# fpga.net
KiCad netlist of a schematic drawn in Altium Designer
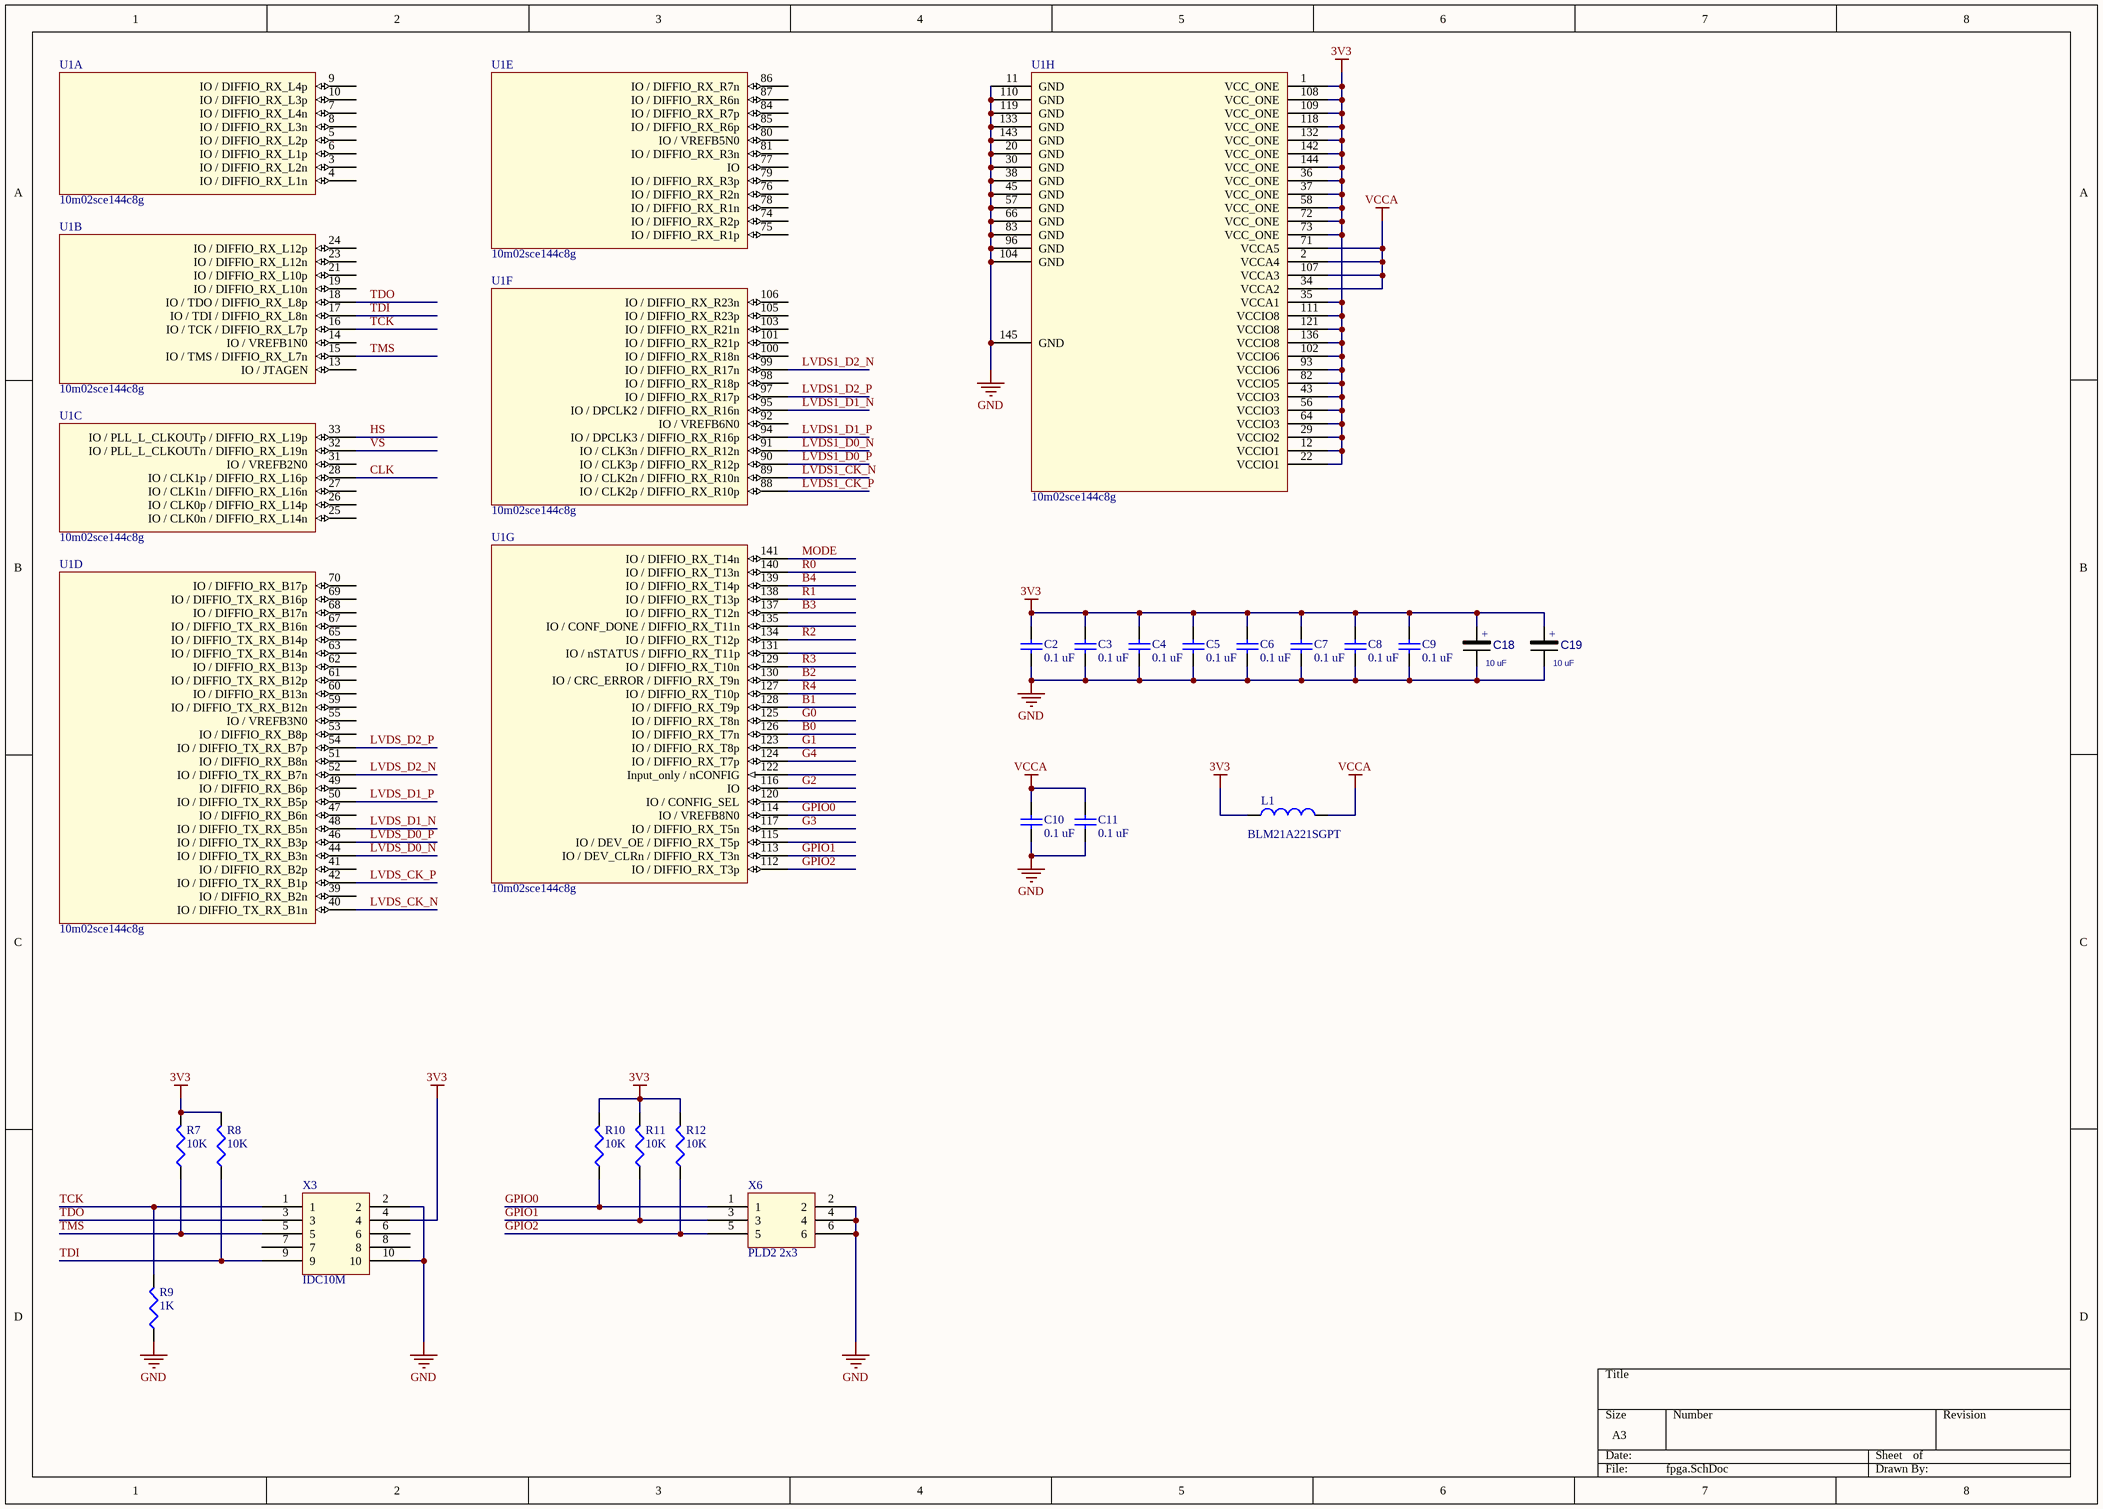
[diagram p0: fpga.SchDoc]

(export (version "E")
  (design (tool "Eeschema 10.0.6"))
  (components
    (comp (ref "C2")
      (value "0.1 uF")
      (footprint "0805 chip cap")
      (description "Capacitor")
      (libsource (lib "Schlib") (part "Cap"))
    )
    (comp (ref "C3")
      (value "0.1 uF")
      (footprint "0805 chip cap")
      (description "Capacitor")
      (libsource (lib "Schlib") (part "Cap"))
    )
    (comp (ref "C4")
      (value "0.1 uF")
      (footprint "0805 chip cap")
      (description "Capacitor")
      (libsource (lib "Schlib") (part "Cap"))
    )
    (comp (ref "C5")
      (value "0.1 uF")
      (footprint "0805 chip cap")
      (description "Capacitor")
      (libsource (lib "Schlib") (part "Cap"))
    )
    (comp (ref "C6")
      (value "0.1 uF")
      (footprint "0805 chip cap")
      (description "Capacitor")
      (libsource (lib "Schlib") (part "Cap"))
    )
    (comp (ref "C7")
      (value "0.1 uF")
      (footprint "0805 chip cap")
      (description "Capacitor")
      (libsource (lib "Schlib") (part "Cap"))
    )
    (comp (ref "C8")
      (value "0.1 uF")
      (footprint "0805 chip cap")
      (description "Capacitor")
      (libsource (lib "Schlib") (part "Cap"))
    )
    (comp (ref "C9")
      (value "0.1 uF")
      (footprint "0805 chip cap")
      (description "Capacitor")
      (libsource (lib "Schlib") (part "Cap"))
    )
    (comp (ref "C10")
      (value "0.1 uF")
      (footprint "0805 chip cap")
      (description "Capacitor")
      (libsource (lib "Schlib") (part "Cap"))
    )
    (comp (ref "C11")
      (value "0.1 uF")
      (footprint "0805 chip cap")
      (description "Capacitor")
      (libsource (lib "Schlib") (part "Cap"))
    )
    (comp (ref "C18")
      (value "10 uF")
      (footprint "CAP CASE-A")
      (libsource (lib "Schlib") (part "CAP POL CASE A"))
    )
    (comp (ref "C19")
      (value "10 uF")
      (footprint "CAP CASE-A")
      (libsource (lib "Schlib") (part "CAP POL CASE A"))
    )
    (comp (ref "L1")
      (value "BLM21A221SGPT")
      (footprint "0805 CHIP RES")
      (description "CHIP FERRITE BEADS 220R AT 100Mhz")
      (libsource (lib "Schlib") (part "BLM21A221SGPT"))
    )
    (comp (ref "R7")
      (value "10K")
      (footprint "0805 CHIP RES")
      (description "Resistor")
      (libsource (lib "Schlib") (part "CHIP RES"))
    )
    (comp (ref "R8")
      (value "10K")
      (footprint "0805 CHIP RES")
      (description "Resistor")
      (libsource (lib "Schlib") (part "CHIP RES"))
    )
    (comp (ref "R9")
      (value "1K")
      (footprint "0805 CHIP RES")
      (description "Resistor")
      (libsource (lib "Schlib") (part "CHIP RES"))
    )
    (comp (ref "R10")
      (value "10K")
      (footprint "0805 CHIP RES")
      (description "Resistor")
      (libsource (lib "Schlib") (part "CHIP RES"))
    )
    (comp (ref "R11")
      (value "10K")
      (footprint "0805 CHIP RES")
      (description "Resistor")
      (libsource (lib "Schlib") (part "CHIP RES"))
    )
    (comp (ref "R12")
      (value "10K")
      (footprint "0805 CHIP RES")
      (description "Resistor")
      (libsource (lib "Schlib") (part "CHIP RES"))
    )
    (comp (ref "U1")
      (value "10m02sce144c8g")
      (footprint "Altera TQFP 50P 22X22 145N")
      (description "FPGA MAX10")
      (libsource (lib "Schlib") (part "10m02sce144c8g"))
    )
    (comp (ref "X3") (value "IDC10M") (footprint "PLD2-10") (libsource (lib "Schlib") (part "PLD2-10")))
    (comp (ref "X6") (value "PLD2 2x3") (footprint "PLD2-6") (libsource (lib "Schlib") (part "PLD2-6")))
  )
  (nets
    (net (code "1") (name "/B0") (class "Default")
      (node (ref "U1") (pin "126") (pinfunction "IO_/_DIFFIO_RX_T7n_126") (pintype "bidirectional"))
    )
    (net (code "2") (name "/B1") (class "Default")
      (node (ref "U1") (pin "128") (pinfunction "IO_/_DIFFIO_RX_T9p_128") (pintype "bidirectional"))
    )
    (net (code "3") (name "/B2") (class "Default")
      (node (ref "U1") (pin "130") (pinfunction "IO_/_CRC_ERROR_/_DIFFIO_RX_T9n_130") (pintype "bidirectional"))
    )
    (net (code "4") (name "/B3") (class "Default")
      (node (ref "U1") (pin "137") (pinfunction "IO_/_DIFFIO_RX_T12n_137") (pintype "bidirectional"))
    )
    (net (code "5") (name "/B4") (class "Default")
      (node (ref "U1") (pin "139") (pinfunction "IO_/_DIFFIO_RX_T14p_139") (pintype "bidirectional"))
    )
    (net (code "6") (name "/CLK") (class "Default")
      (node (ref "U1") (pin "28") (pinfunction "IO_/_CLK1p_/_DIFFIO_RX_L16p_28") (pintype "bidirectional"))
    )
    (net (code "7") (name "/G0") (class "Default")
      (node (ref "U1") (pin "125") (pinfunction "IO_/_DIFFIO_RX_T8n_125") (pintype "bidirectional"))
    )
    (net (code "8") (name "/G1") (class "Default")
      (node (ref "U1") (pin "123") (pinfunction "IO_/_DIFFIO_RX_T8p_123") (pintype "bidirectional"))
    )
    (net (code "9") (name "/G2") (class "Default")
      (node (ref "U1") (pin "116") (pinfunction "IO_116") (pintype "bidirectional"))
    )
    (net (code "10") (name "/G3") (class "Default")
      (node (ref "U1") (pin "117") (pinfunction "IO_/_DIFFIO_RX_T5n_117") (pintype "bidirectional"))
    )
    (net (code "11") (name "/G4") (class "Default")
      (node (ref "U1") (pin "124") (pinfunction "IO_/_DIFFIO_RX_T7p_124") (pintype "bidirectional"))
    )
    (net (code "12") (name "/GPIO0") (class "Default")
      (node (ref "R10") (pin "1") (pinfunction "1_1") (pintype "passive"))
      (node (ref "U1") (pin "114") (pinfunction "IO_/_VREFB8N0_114") (pintype "bidirectional"))
      (node (ref "X6") (pin "1") (pinfunction "1_1") (pintype "passive"))
    )
    (net (code "13") (name "/GPIO1") (class "Default")
      (node (ref "R11") (pin "1") (pinfunction "1_1") (pintype "passive"))
      (node (ref "U1") (pin "113") (pinfunction "IO_/_DEV_CLRn_/_DIFFIO_RX_T3n_113") (pintype "bidirectional"))
      (node (ref "X6") (pin "3") (pinfunction "3_3") (pintype "passive"))
    )
    (net (code "14") (name "/GPIO2") (class "Default")
      (node (ref "R12") (pin "1") (pinfunction "1_1") (pintype "passive"))
      (node (ref "U1") (pin "112") (pinfunction "IO_/_DIFFIO_RX_T3p_112") (pintype "bidirectional"))
      (node (ref "X6") (pin "5") (pinfunction "5_5") (pintype "passive"))
    )
    (net (code "15") (name "/HS") (class "Default")
      (node (ref "U1") (pin "33") (pinfunction "IO_/_PLL_L_CLKOUTp_/_DIFFIO_RX_L19p_33") (pintype "bidirectional"))
    )
    (net (code "16") (name "/LVDS1_CK_N") (class "Default")
      (node (ref "U1") (pin "89") (pinfunction "IO_/_CLK2n_/_DIFFIO_RX_R10n_89") (pintype "bidirectional"))
    )
    (net (code "17") (name "/LVDS1_CK_P") (class "Default")
      (node (ref "U1") (pin "88") (pinfunction "IO_/_CLK2p_/_DIFFIO_RX_R10p_88") (pintype "bidirectional"))
    )
    (net (code "18") (name "/LVDS1_D0_N") (class "Default")
      (node (ref "U1") (pin "91") (pinfunction "IO_/_CLK3n_/_DIFFIO_RX_R12n_91") (pintype "bidirectional"))
    )
    (net (code "19") (name "/LVDS1_D0_P") (class "Default")
      (node (ref "U1") (pin "90") (pinfunction "IO_/_CLK3p_/_DIFFIO_RX_R12p_90") (pintype "bidirectional"))
    )
    (net (code "20") (name "/LVDS1_D1_N") (class "Default")
      (node (ref "U1") (pin "95") (pinfunction "IO_/_DPCLK2_/_DIFFIO_RX_R16n_95") (pintype "bidirectional"))
    )
    (net (code "21") (name "/LVDS1_D1_P") (class "Default")
      (node (ref "U1") (pin "94") (pinfunction "IO_/_DPCLK3_/_DIFFIO_RX_R16p_94") (pintype "bidirectional"))
    )
    (net (code "22") (name "/LVDS1_D2_N") (class "Default")
      (node (ref "U1") (pin "99") (pinfunction "IO_/_DIFFIO_RX_R17n_99") (pintype "bidirectional"))
    )
    (net (code "23") (name "/LVDS1_D2_P") (class "Default")
      (node (ref "U1") (pin "97") (pinfunction "IO_/_DIFFIO_RX_R17p_97") (pintype "bidirectional"))
    )
    (net (code "24") (name "/LVDS_CK_N") (class "Default")
      (node (ref "U1") (pin "40") (pinfunction "IO_/_DIFFIO_TX_RX_B1n_40") (pintype "bidirectional"))
    )
    (net (code "25") (name "/LVDS_CK_P") (class "Default")
      (node (ref "U1") (pin "42") (pinfunction "IO_/_DIFFIO_TX_RX_B1p_42") (pintype "bidirectional"))
    )
    (net (code "26") (name "/LVDS_D0_N") (class "Default")
      (node (ref "U1") (pin "44") (pinfunction "IO_/_DIFFIO_TX_RX_B3n_44") (pintype "bidirectional"))
    )
    (net (code "27") (name "/LVDS_D0_P") (class "Default")
      (node (ref "U1") (pin "46") (pinfunction "IO_/_DIFFIO_TX_RX_B3p_46") (pintype "bidirectional"))
    )
    (net (code "28") (name "/LVDS_D1_N") (class "Default")
      (node (ref "U1") (pin "48") (pinfunction "IO_/_DIFFIO_TX_RX_B5n_48") (pintype "bidirectional"))
    )
    (net (code "29") (name "/LVDS_D1_P") (class "Default")
      (node (ref "U1") (pin "50") (pinfunction "IO_/_DIFFIO_TX_RX_B5p_50") (pintype "bidirectional"))
    )
    (net (code "30") (name "/LVDS_D2_N") (class "Default")
      (node (ref "U1") (pin "52") (pinfunction "IO_/_DIFFIO_TX_RX_B7n_52") (pintype "bidirectional"))
    )
    (net (code "31") (name "/LVDS_D2_P") (class "Default")
      (node (ref "U1") (pin "54") (pinfunction "IO_/_DIFFIO_TX_RX_B7p_54") (pintype "bidirectional"))
    )
    (net (code "32") (name "/MODE") (class "Default")
      (node (ref "U1") (pin "141") (pinfunction "IO_/_DIFFIO_RX_T14n_141") (pintype "bidirectional"))
    )
    (net (code "33") (name "/R0") (class "Default")
      (node (ref "U1") (pin "140") (pinfunction "IO_/_DIFFIO_RX_T13n_140") (pintype "bidirectional"))
    )
    (net (code "34") (name "/R1") (class "Default")
      (node (ref "U1") (pin "138") (pinfunction "IO_/_DIFFIO_RX_T13p_138") (pintype "bidirectional"))
    )
    (net (code "35") (name "/R2") (class "Default")
      (node (ref "U1") (pin "134") (pinfunction "IO_/_DIFFIO_RX_T12p_134") (pintype "bidirectional"))
    )
    (net (code "36") (name "/R3") (class "Default")
      (node (ref "U1") (pin "129") (pinfunction "IO_/_DIFFIO_RX_T10n_129") (pintype "bidirectional"))
    )
    (net (code "37") (name "/R4") (class "Default")
      (node (ref "U1") (pin "127") (pinfunction "IO_/_DIFFIO_RX_T10p_127") (pintype "bidirectional"))
    )
    (net (code "38") (name "/TCK") (class "Default")
      (node (ref "R9") (pin "2") (pinfunction "2_2") (pintype "passive"))
      (node (ref "U1") (pin "16") (pinfunction "IO_/_TCK_/_DIFFIO_RX_L7p_16") (pintype "bidirectional"))
      (node (ref "X3") (pin "1") (pinfunction "1_1") (pintype "passive"))
    )
    (net (code "39") (name "/TDI") (class "Default")
      (node (ref "R8") (pin "1") (pinfunction "1_1") (pintype "passive"))
      (node (ref "U1") (pin "17") (pinfunction "IO_/_TDI_/_DIFFIO_RX_L8n_17") (pintype "bidirectional"))
      (node (ref "X3") (pin "9") (pinfunction "9_9") (pintype "passive"))
    )
    (net (code "40") (name "/TDO") (class "Default")
      (node (ref "U1") (pin "18") (pinfunction "IO_/_TDO_/_DIFFIO_RX_L8p_18") (pintype "bidirectional"))
      (node (ref "X3") (pin "3") (pinfunction "3_3") (pintype "passive"))
    )
    (net (code "41") (name "/TMS") (class "Default")
      (node (ref "R7") (pin "1") (pinfunction "1_1") (pintype "passive"))
      (node (ref "U1") (pin "15") (pinfunction "IO_/_TMS_/_DIFFIO_RX_L7n_15") (pintype "bidirectional"))
      (node (ref "X3") (pin "5") (pinfunction "5_5") (pintype "passive"))
    )
    (net (code "42") (name "/VS") (class "Default")
      (node (ref "U1") (pin "32") (pinfunction "IO_/_PLL_L_CLKOUTn_/_DIFFIO_RX_L19n_32") (pintype "bidirectional"))
    )
    (net (code "43") (name "3V3") (class "Default")
      (node (ref "C18") (pin "1") (pinfunction "1_1") (pintype "passive"))
      (node (ref "C19") (pin "1") (pinfunction "1_1") (pintype "passive"))
      (node (ref "C2") (pin "2") (pinfunction "2_2") (pintype "passive"))
      (node (ref "C3") (pin "2") (pinfunction "2_2") (pintype "passive"))
      (node (ref "C4") (pin "2") (pinfunction "2_2") (pintype "passive"))
      (node (ref "C5") (pin "2") (pinfunction "2_2") (pintype "passive"))
      (node (ref "C6") (pin "2") (pinfunction "2_2") (pintype "passive"))
      (node (ref "C7") (pin "2") (pinfunction "2_2") (pintype "passive"))
      (node (ref "C8") (pin "2") (pinfunction "2_2") (pintype "passive"))
      (node (ref "C9") (pin "2") (pinfunction "2_2") (pintype "passive"))
      (node (ref "L1") (pin "1") (pinfunction "1_1") (pintype "passive"))
      (node (ref "R10") (pin "2") (pinfunction "2_2") (pintype "passive"))
      (node (ref "R11") (pin "2") (pinfunction "2_2") (pintype "passive"))
      (node (ref "R12") (pin "2") (pinfunction "2_2") (pintype "passive"))
      (node (ref "R7") (pin "2") (pinfunction "2_2") (pintype "passive"))
      (node (ref "R8") (pin "2") (pinfunction "2_2") (pintype "passive"))
      (node (ref "U1") (pin "1") (pinfunction "VCC_ONE_1") (pintype "power_in"))
      (node (ref "U1") (pin "102") (pinfunction "VCCIO6_102") (pintype "power_in"))
      (node (ref "U1") (pin "108") (pinfunction "VCC_ONE_108") (pintype "power_in"))
      (node (ref "U1") (pin "109") (pinfunction "VCC_ONE_109") (pintype "power_in"))
      (node (ref "U1") (pin "111") (pinfunction "VCCIO8_111") (pintype "power_in"))
      (node (ref "U1") (pin "118") (pinfunction "VCC_ONE_118") (pintype "power_in"))
      (node (ref "U1") (pin "12") (pinfunction "VCCIO1_12") (pintype "power_in"))
      (node (ref "U1") (pin "121") (pinfunction "VCCIO8_121") (pintype "power_in"))
      (node (ref "U1") (pin "132") (pinfunction "VCC_ONE_132") (pintype "power_in"))
      (node (ref "U1") (pin "136") (pinfunction "VCCIO8_136") (pintype "power_in"))
      (node (ref "U1") (pin "142") (pinfunction "VCC_ONE_142") (pintype "power_in"))
      (node (ref "U1") (pin "144") (pinfunction "VCC_ONE_144") (pintype "power_in"))
      (node (ref "U1") (pin "22") (pinfunction "VCCIO1_22") (pintype "power_in"))
      (node (ref "U1") (pin "29") (pinfunction "VCCIO2_29") (pintype "power_in"))
      (node (ref "U1") (pin "35") (pinfunction "VCCA1_35") (pintype "power_in"))
      (node (ref "U1") (pin "36") (pinfunction "VCC_ONE_36") (pintype "power_in"))
      (node (ref "U1") (pin "37") (pinfunction "VCC_ONE_37") (pintype "power_in"))
      (node (ref "U1") (pin "43") (pinfunction "VCCIO3_43") (pintype "power_in"))
      (node (ref "U1") (pin "56") (pinfunction "VCCIO3_56") (pintype "power_in"))
      (node (ref "U1") (pin "58") (pinfunction "VCC_ONE_58") (pintype "power_in"))
      (node (ref "U1") (pin "64") (pinfunction "VCCIO3_64") (pintype "power_in"))
      (node (ref "U1") (pin "72") (pinfunction "VCC_ONE_72") (pintype "power_in"))
      (node (ref "U1") (pin "73") (pinfunction "VCC_ONE_73") (pintype "power_in"))
      (node (ref "U1") (pin "82") (pinfunction "VCCIO5_82") (pintype "power_in"))
      (node (ref "U1") (pin "93") (pinfunction "VCCIO6_93") (pintype "power_in"))
      (node (ref "X3") (pin "4") (pinfunction "4_4") (pintype "passive"))
    )
    (net (code "44") (name "GND") (class "Default")
      (node (ref "C10") (pin "1") (pinfunction "1_1") (pintype "passive"))
      (node (ref "C11") (pin "1") (pinfunction "1_1") (pintype "passive"))
      (node (ref "C18") (pin "2") (pinfunction "2_2") (pintype "passive"))
      (node (ref "C19") (pin "2") (pinfunction "2_2") (pintype "passive"))
      (node (ref "C2") (pin "1") (pinfunction "1_1") (pintype "passive"))
      (node (ref "C3") (pin "1") (pinfunction "1_1") (pintype "passive"))
      (node (ref "C4") (pin "1") (pinfunction "1_1") (pintype "passive"))
      (node (ref "C5") (pin "1") (pinfunction "1_1") (pintype "passive"))
      (node (ref "C6") (pin "1") (pinfunction "1_1") (pintype "passive"))
      (node (ref "C7") (pin "1") (pinfunction "1_1") (pintype "passive"))
      (node (ref "C8") (pin "1") (pinfunction "1_1") (pintype "passive"))
      (node (ref "C9") (pin "1") (pinfunction "1_1") (pintype "passive"))
      (node (ref "R9") (pin "1") (pinfunction "1_1") (pintype "passive"))
      (node (ref "U1") (pin "104") (pinfunction "GND_104") (pintype "power_in"))
      (node (ref "U1") (pin "11") (pinfunction "GND_11") (pintype "power_in"))
      (node (ref "U1") (pin "110") (pinfunction "GND_110") (pintype "power_in"))
      (node (ref "U1") (pin "119") (pinfunction "GND_119") (pintype "power_in"))
      (node (ref "U1") (pin "133") (pinfunction "GND_133") (pintype "power_in"))
      (node (ref "U1") (pin "143") (pinfunction "GND_143") (pintype "power_in"))
      (node (ref "U1") (pin "145") (pinfunction "GND_145") (pintype "power_in"))
      (node (ref "U1") (pin "20") (pinfunction "GND_20") (pintype "power_in"))
      (node (ref "U1") (pin "30") (pinfunction "GND_30") (pintype "power_in"))
      (node (ref "U1") (pin "38") (pinfunction "GND_38") (pintype "power_in"))
      (node (ref "U1") (pin "45") (pinfunction "GND_45") (pintype "power_in"))
      (node (ref "U1") (pin "57") (pinfunction "GND_57") (pintype "power_in"))
      (node (ref "U1") (pin "66") (pinfunction "GND_66") (pintype "power_in"))
      (node (ref "U1") (pin "83") (pinfunction "GND_83") (pintype "power_in"))
      (node (ref "U1") (pin "96") (pinfunction "GND_96") (pintype "power_in"))
      (node (ref "X3") (pin "10") (pinfunction "10_10") (pintype "passive"))
      (node (ref "X3") (pin "2") (pinfunction "2_2") (pintype "passive"))
      (node (ref "X6") (pin "2") (pinfunction "2_2") (pintype "passive"))
      (node (ref "X6") (pin "4") (pinfunction "4_4") (pintype "passive"))
      (node (ref "X6") (pin "6") (pinfunction "6_6") (pintype "passive"))
    )
    (net (code "45") (name "VCCA") (class "Default")
      (node (ref "C10") (pin "2") (pinfunction "2_2") (pintype "passive"))
      (node (ref "C11") (pin "2") (pinfunction "2_2") (pintype "passive"))
      (node (ref "L1") (pin "2") (pinfunction "2_2") (pintype "passive"))
      (node (ref "U1") (pin "107") (pinfunction "VCCA3_107") (pintype "power_in"))
      (node (ref "U1") (pin "2") (pinfunction "VCCA4_2") (pintype "power_in"))
      (node (ref "U1") (pin "34") (pinfunction "VCCA2_34") (pintype "power_in"))
      (node (ref "U1") (pin "71") (pinfunction "VCCA5_71") (pintype "power_in"))
    )
    (net (code "46") (name "unconnected-(U1A-IO_{slash}_DIFFIO_RX_L1n-Pad4)") (class "Default")
      (node (ref "U1") (pin "4") (pinfunction "IO_/_DIFFIO_RX_L1n_4") (pintype "bidirectional"))
    )
    (net (code "47") (name "unconnected-(U1A-IO_{slash}_DIFFIO_RX_L1p-Pad6)") (class "Default")
      (node (ref "U1") (pin "6") (pinfunction "IO_/_DIFFIO_RX_L1p_6") (pintype "bidirectional"))
    )
    (net (code "48") (name "unconnected-(U1A-IO_{slash}_DIFFIO_RX_L2n-Pad3)") (class "Default")
      (node (ref "U1") (pin "3") (pinfunction "IO_/_DIFFIO_RX_L2n_3") (pintype "bidirectional"))
    )
    (net (code "49") (name "unconnected-(U1A-IO_{slash}_DIFFIO_RX_L2p-Pad5)") (class "Default")
      (node (ref "U1") (pin "5") (pinfunction "IO_/_DIFFIO_RX_L2p_5") (pintype "bidirectional"))
    )
    (net (code "50") (name "unconnected-(U1A-IO_{slash}_DIFFIO_RX_L3n-Pad8)") (class "Default")
      (node (ref "U1") (pin "8") (pinfunction "IO_/_DIFFIO_RX_L3n_8") (pintype "bidirectional"))
    )
    (net (code "51") (name "unconnected-(U1A-IO_{slash}_DIFFIO_RX_L3p-Pad10)") (class "Default")
      (node (ref "U1") (pin "10") (pinfunction "IO_/_DIFFIO_RX_L3p_10") (pintype "bidirectional"))
    )
    (net (code "52") (name "unconnected-(U1A-IO_{slash}_DIFFIO_RX_L4n-Pad7)") (class "Default")
      (node (ref "U1") (pin "7") (pinfunction "IO_/_DIFFIO_RX_L4n_7") (pintype "bidirectional"))
    )
    (net (code "53") (name "unconnected-(U1A-IO_{slash}_DIFFIO_RX_L4p-Pad9)") (class "Default")
      (node (ref "U1") (pin "9") (pinfunction "IO_/_DIFFIO_RX_L4p_9") (pintype "bidirectional"))
    )
    (net (code "54") (name "unconnected-(U1B-IO_{slash}_DIFFIO_RX_L10n-Pad19)") (class "Default")
      (node (ref "U1") (pin "19") (pinfunction "IO_/_DIFFIO_RX_L10n_19") (pintype "bidirectional"))
    )
    (net (code "55") (name "unconnected-(U1B-IO_{slash}_DIFFIO_RX_L10p-Pad21)") (class "Default")
      (node (ref "U1") (pin "21") (pinfunction "IO_/_DIFFIO_RX_L10p_21") (pintype "bidirectional"))
    )
    (net (code "56") (name "unconnected-(U1B-IO_{slash}_DIFFIO_RX_L12n-Pad23)") (class "Default")
      (node (ref "U1") (pin "23") (pinfunction "IO_/_DIFFIO_RX_L12n_23") (pintype "bidirectional"))
    )
    (net (code "57") (name "unconnected-(U1B-IO_{slash}_DIFFIO_RX_L12p-Pad24)") (class "Default")
      (node (ref "U1") (pin "24") (pinfunction "IO_/_DIFFIO_RX_L12p_24") (pintype "bidirectional"))
    )
    (net (code "58") (name "unconnected-(U1B-IO_{slash}_JTAGEN-Pad13)") (class "Default")
      (node (ref "U1") (pin "13") (pinfunction "IO_/_JTAGEN_13") (pintype "bidirectional"))
    )
    (net (code "59") (name "unconnected-(U1B-IO_{slash}_VREFB1N0-Pad14)") (class "Default")
      (node (ref "U1") (pin "14") (pinfunction "IO_/_VREFB1N0_14") (pintype "bidirectional"))
    )
    (net (code "60") (name "unconnected-(U1C-IO_{slash}_CLK0n_{slash}_DIFFIO_RX_L14n-Pad25)") (class "Default")
      (node (ref "U1") (pin "25") (pinfunction "IO_/_CLK0n_/_DIFFIO_RX_L14n_25") (pintype "bidirectional"))
    )
    (net (code "61") (name "unconnected-(U1C-IO_{slash}_CLK0p_{slash}_DIFFIO_RX_L14p-Pad26)") (class "Default")
      (node (ref "U1") (pin "26") (pinfunction "IO_/_CLK0p_/_DIFFIO_RX_L14p_26") (pintype "bidirectional"))
    )
    (net (code "62") (name "unconnected-(U1C-IO_{slash}_CLK1n_{slash}_DIFFIO_RX_L16n-Pad27)") (class "Default")
      (node (ref "U1") (pin "27") (pinfunction "IO_/_CLK1n_/_DIFFIO_RX_L16n_27") (pintype "bidirectional"))
    )
    (net (code "63") (name "unconnected-(U1C-IO_{slash}_VREFB2N0-Pad31)") (class "Default")
      (node (ref "U1") (pin "31") (pinfunction "IO_/_VREFB2N0_31") (pintype "bidirectional"))
    )
    (net (code "64") (name "unconnected-(U1D-IO_{slash}_DIFFIO_RX_B2n-Pad39)") (class "Default")
      (node (ref "U1") (pin "39") (pinfunction "IO_/_DIFFIO_RX_B2n_39") (pintype "bidirectional"))
    )
    (net (code "65") (name "unconnected-(U1D-IO_{slash}_DIFFIO_RX_B2p-Pad41)") (class "Default")
      (node (ref "U1") (pin "41") (pinfunction "IO_/_DIFFIO_RX_B2p_41") (pintype "bidirectional"))
    )
    (net (code "66") (name "unconnected-(U1D-IO_{slash}_DIFFIO_RX_B6n-Pad47)") (class "Default")
      (node (ref "U1") (pin "47") (pinfunction "IO_/_DIFFIO_RX_B6n_47") (pintype "bidirectional"))
    )
    (net (code "67") (name "unconnected-(U1D-IO_{slash}_DIFFIO_RX_B6p-Pad49)") (class "Default")
      (node (ref "U1") (pin "49") (pinfunction "IO_/_DIFFIO_RX_B6p_49") (pintype "bidirectional"))
    )
    (net (code "68") (name "unconnected-(U1D-IO_{slash}_DIFFIO_RX_B8n-Pad51)") (class "Default")
      (node (ref "U1") (pin "51") (pinfunction "IO_/_DIFFIO_RX_B8n_51") (pintype "bidirectional"))
    )
    (net (code "69") (name "unconnected-(U1D-IO_{slash}_DIFFIO_RX_B8p-Pad53)") (class "Default")
      (node (ref "U1") (pin "53") (pinfunction "IO_/_DIFFIO_RX_B8p_53") (pintype "bidirectional"))
    )
    (net (code "70") (name "unconnected-(U1D-IO_{slash}_DIFFIO_RX_B13n-Pad60)") (class "Default")
      (node (ref "U1") (pin "60") (pinfunction "IO_/_DIFFIO_RX_B13n_60") (pintype "bidirectional"))
    )
    (net (code "71") (name "unconnected-(U1D-IO_{slash}_DIFFIO_RX_B13p-Pad62)") (class "Default")
      (node (ref "U1") (pin "62") (pinfunction "IO_/_DIFFIO_RX_B13p_62") (pintype "bidirectional"))
    )
    (net (code "72") (name "unconnected-(U1D-IO_{slash}_DIFFIO_RX_B17n-Pad68)") (class "Default")
      (node (ref "U1") (pin "68") (pinfunction "IO_/_DIFFIO_RX_B17n_68") (pintype "bidirectional"))
    )
    (net (code "73") (name "unconnected-(U1D-IO_{slash}_DIFFIO_RX_B17p-Pad70)") (class "Default")
      (node (ref "U1") (pin "70") (pinfunction "IO_/_DIFFIO_RX_B17p_70") (pintype "bidirectional"))
    )
    (net (code "74") (name "unconnected-(U1D-IO_{slash}_DIFFIO_TX_RX_B12n-Pad59)") (class "Default")
      (node (ref "U1") (pin "59") (pinfunction "IO_/_DIFFIO_TX_RX_B12n_59") (pintype "bidirectional"))
    )
    (net (code "75") (name "unconnected-(U1D-IO_{slash}_DIFFIO_TX_RX_B12p-Pad61)") (class "Default")
      (node (ref "U1") (pin "61") (pinfunction "IO_/_DIFFIO_TX_RX_B12p_61") (pintype "bidirectional"))
    )
    (net (code "76") (name "unconnected-(U1D-IO_{slash}_DIFFIO_TX_RX_B14n-Pad63)") (class "Default")
      (node (ref "U1") (pin "63") (pinfunction "IO_/_DIFFIO_TX_RX_B14n_63") (pintype "bidirectional"))
    )
    (net (code "77") (name "unconnected-(U1D-IO_{slash}_DIFFIO_TX_RX_B14p-Pad65)") (class "Default")
      (node (ref "U1") (pin "65") (pinfunction "IO_/_DIFFIO_TX_RX_B14p_65") (pintype "bidirectional"))
    )
    (net (code "78") (name "unconnected-(U1D-IO_{slash}_DIFFIO_TX_RX_B16n-Pad67)") (class "Default")
      (node (ref "U1") (pin "67") (pinfunction "IO_/_DIFFIO_TX_RX_B16n_67") (pintype "bidirectional"))
    )
    (net (code "79") (name "unconnected-(U1D-IO_{slash}_DIFFIO_TX_RX_B16p-Pad69)") (class "Default")
      (node (ref "U1") (pin "69") (pinfunction "IO_/_DIFFIO_TX_RX_B16p_69") (pintype "bidirectional"))
    )
    (net (code "80") (name "unconnected-(U1D-IO_{slash}_VREFB3N0-Pad55)") (class "Default")
      (node (ref "U1") (pin "55") (pinfunction "IO_/_VREFB3N0_55") (pintype "bidirectional"))
    )
    (net (code "81") (name "unconnected-(U1E-IO-Pad77)") (class "Default")
      (node (ref "U1") (pin "77") (pinfunction "IO_77") (pintype "bidirectional"))
    )
    (net (code "82") (name "unconnected-(U1E-IO_{slash}_DIFFIO_RX_R1n-Pad78)") (class "Default")
      (node (ref "U1") (pin "78") (pinfunction "IO_/_DIFFIO_RX_R1n_78") (pintype "bidirectional"))
    )
    (net (code "83") (name "unconnected-(U1E-IO_{slash}_DIFFIO_RX_R1p-Pad75)") (class "Default")
      (node (ref "U1") (pin "75") (pinfunction "IO_/_DIFFIO_RX_R1p_75") (pintype "bidirectional"))
    )
    (net (code "84") (name "unconnected-(U1E-IO_{slash}_DIFFIO_RX_R2n-Pad76)") (class "Default")
      (node (ref "U1") (pin "76") (pinfunction "IO_/_DIFFIO_RX_R2n_76") (pintype "bidirectional"))
    )
    (net (code "85") (name "unconnected-(U1E-IO_{slash}_DIFFIO_RX_R2p-Pad74)") (class "Default")
      (node (ref "U1") (pin "74") (pinfunction "IO_/_DIFFIO_RX_R2p_74") (pintype "bidirectional"))
    )
    (net (code "86") (name "unconnected-(U1E-IO_{slash}_DIFFIO_RX_R3n-Pad81)") (class "Default")
      (node (ref "U1") (pin "81") (pinfunction "IO_/_DIFFIO_RX_R3n_81") (pintype "bidirectional"))
    )
    (net (code "87") (name "unconnected-(U1E-IO_{slash}_DIFFIO_RX_R3p-Pad79)") (class "Default")
      (node (ref "U1") (pin "79") (pinfunction "IO_/_DIFFIO_RX_R3p_79") (pintype "bidirectional"))
    )
    (net (code "88") (name "unconnected-(U1E-IO_{slash}_DIFFIO_RX_R6n-Pad87)") (class "Default")
      (node (ref "U1") (pin "87") (pinfunction "IO_/_DIFFIO_RX_R6n_87") (pintype "bidirectional"))
    )
    (net (code "89") (name "unconnected-(U1E-IO_{slash}_DIFFIO_RX_R6p-Pad85)") (class "Default")
      (node (ref "U1") (pin "85") (pinfunction "IO_/_DIFFIO_RX_R6p_85") (pintype "bidirectional"))
    )
    (net (code "90") (name "unconnected-(U1E-IO_{slash}_DIFFIO_RX_R7n-Pad86)") (class "Default")
      (node (ref "U1") (pin "86") (pinfunction "IO_/_DIFFIO_RX_R7n_86") (pintype "bidirectional"))
    )
    (net (code "91") (name "unconnected-(U1E-IO_{slash}_DIFFIO_RX_R7p-Pad84)") (class "Default")
      (node (ref "U1") (pin "84") (pinfunction "IO_/_DIFFIO_RX_R7p_84") (pintype "bidirectional"))
    )
    (net (code "92") (name "unconnected-(U1E-IO_{slash}_VREFB5N0-Pad80)") (class "Default")
      (node (ref "U1") (pin "80") (pinfunction "IO_/_VREFB5N0_80") (pintype "bidirectional"))
    )
    (net (code "93") (name "unconnected-(U1F-IO_{slash}_DIFFIO_RX_R18n-Pad100)") (class "Default")
      (node (ref "U1") (pin "100") (pinfunction "IO_/_DIFFIO_RX_R18n_100") (pintype "bidirectional"))
    )
    (net (code "94") (name "unconnected-(U1F-IO_{slash}_DIFFIO_RX_R18p-Pad98)") (class "Default")
      (node (ref "U1") (pin "98") (pinfunction "IO_/_DIFFIO_RX_R18p_98") (pintype "bidirectional"))
    )
    (net (code "95") (name "unconnected-(U1F-IO_{slash}_DIFFIO_RX_R21n-Pad103)") (class "Default")
      (node (ref "U1") (pin "103") (pinfunction "IO_/_DIFFIO_RX_R21n_103") (pintype "bidirectional"))
    )
    (net (code "96") (name "unconnected-(U1F-IO_{slash}_DIFFIO_RX_R21p-Pad101)") (class "Default")
      (node (ref "U1") (pin "101") (pinfunction "IO_/_DIFFIO_RX_R21p_101") (pintype "bidirectional"))
    )
    (net (code "97") (name "unconnected-(U1F-IO_{slash}_DIFFIO_RX_R23n-Pad106)") (class "Default")
      (node (ref "U1") (pin "106") (pinfunction "IO_/_DIFFIO_RX_R23n_106") (pintype "bidirectional"))
    )
    (net (code "98") (name "unconnected-(U1F-IO_{slash}_DIFFIO_RX_R23p-Pad105)") (class "Default")
      (node (ref "U1") (pin "105") (pinfunction "IO_/_DIFFIO_RX_R23p_105") (pintype "bidirectional"))
    )
    (net (code "99") (name "unconnected-(U1F-IO_{slash}_VREFB6N0-Pad92)") (class "Default")
      (node (ref "U1") (pin "92") (pinfunction "IO_/_VREFB6N0_92") (pintype "bidirectional"))
    )
    (net (code "100") (name "unconnected-(U1G-IO_{slash}_CONFIG_SEL-Pad120)") (class "Default")
      (node (ref "U1") (pin "120") (pinfunction "IO_/_CONFIG_SEL_120") (pintype "bidirectional"))
    )
    (net (code "101") (name "unconnected-(U1G-IO_{slash}_CONF_DONE_{slash}_DIFFIO_RX_T11n-Pad135)") (class "Default")
      (node (ref "U1") (pin "135") (pinfunction "IO_/_CONF_DONE_/_DIFFIO_RX_T11n_135") (pintype "bidirectional"))
    )
    (net (code "102") (name "unconnected-(U1G-IO_{slash}_DEV_OE_{slash}_DIFFIO_RX_T5p-Pad115)") (class "Default")
      (node (ref "U1") (pin "115") (pinfunction "IO_/_DEV_OE_/_DIFFIO_RX_T5p_115") (pintype "bidirectional"))
    )
    (net (code "103") (name "unconnected-(U1G-IO_{slash}_nSTATUS_{slash}_DIFFIO_RX_T11p-Pad131)") (class "Default")
      (node (ref "U1") (pin "131") (pinfunction "IO_/_nSTATUS_/_DIFFIO_RX_T11p_131") (pintype "bidirectional"))
    )
    (net (code "104") (name "unconnected-(U1G-Input_only_{slash}_nCONFIG-Pad122)") (class "Default")
      (node (ref "U1") (pin "122") (pinfunction "Input_only_/_nCONFIG_122") (pintype "input"))
    )
    (net (code "105") (name "unconnected-(X3-Pad6)") (class "Default")
      (node (ref "X3") (pin "6") (pinfunction "6_6") (pintype "passive"))
    )
    (net (code "106") (name "unconnected-(X3-Pad7)") (class "Default")
      (node (ref "X3") (pin "7") (pinfunction "7_7") (pintype "passive"))
    )
    (net (code "107") (name "unconnected-(X3-Pad8)") (class "Default")
      (node (ref "X3") (pin "8") (pinfunction "8_8") (pintype "passive"))
    )
  )
)
